# chipshouter-pico-hv.net
KiCad netlist of a schematic drawn in Altium Designer
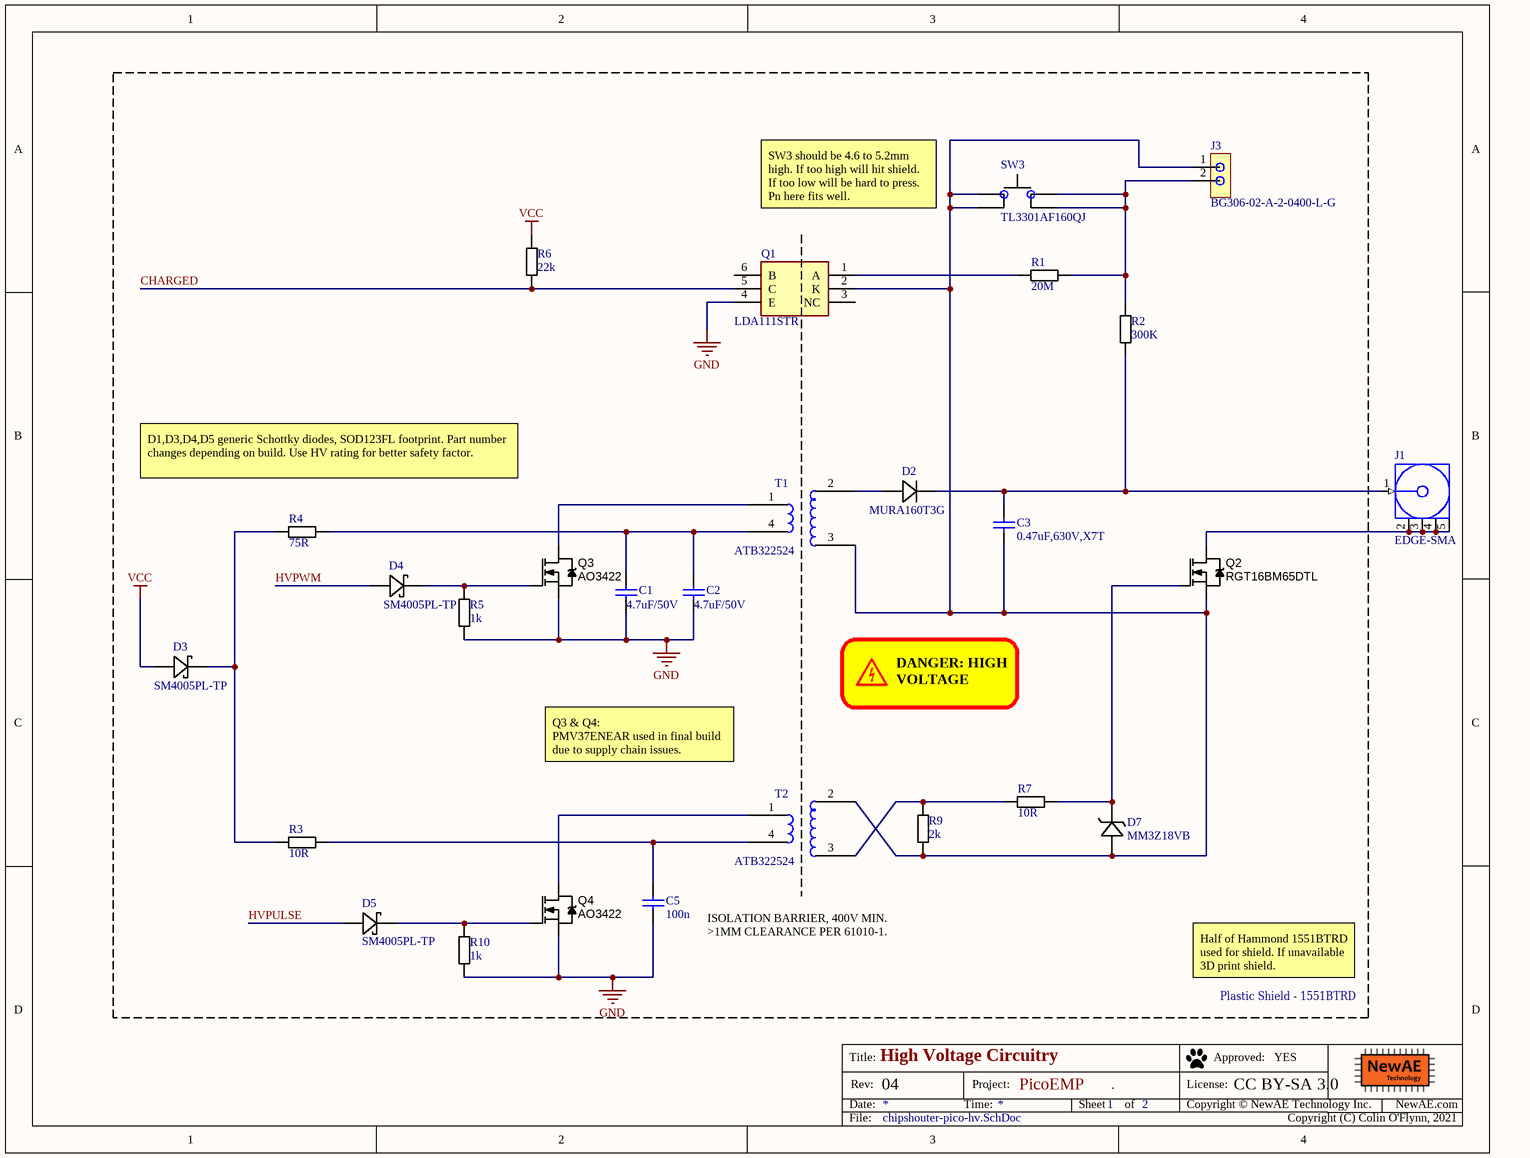
[diagram p0: chipshouter-pico-hv.SchDoc]

(export (version "E")
  (design (tool "Eeschema 10.0.6"))
  (components
    (comp (ref "C1")
      (value "4.7uF/50V")
      (footprint "CAPC0805_M")
      (description "4u7, 50V, 0805, Ceramic")
      (fields (field (name "PART NUMBER") "CCHIP-4u7-0805-50V") (field (name "TOLERANCE") "10%"))
      (libsource (lib "NewAE_AltiumLib") (part "CAP"))
    )
    (comp (ref "C2")
      (value "4.7uF/50V")
      (footprint "CAPC0805_M")
      (description "4u7, 50V, 0805, Ceramic")
      (fields (field (name "PART NUMBER") "CCHIP-4u7-0805-50V") (field (name "TOLERANCE") "10%"))
      (libsource (lib "NewAE_AltiumLib") (part "CAP"))
    )
    (comp (ref "C3")
      (value "0.47uF,630V,X7T")
      (footprint "CKG57N_2220")
      (description "1uF, 630V, X7T, Stacked")
      (fields (field (name "PART NUMBER") "KRM55TR72J474MH01K") (field (name "TOLERANCE") "+22/-30"))
      (libsource (lib "NewAE_AltiumLib") (part "CAP"))
    )
    (comp (ref "C5")
      (value "100n")
      (footprint "CAPC0603_M")
      (description "100n, 0603")
      (fields (field (name "PART NUMBER") "CCHIP-100n-0603"))
      (libsource (lib "NewAE_AltiumLib") (part "CAP"))
    )
    (comp (ref "D2")
      (value "MURA160T3G")
      (footprint "DO-214AC")
      (description "600V, 2A, Fast Recovery Diode")
      (libsource (lib "NewAE_AltiumLib") (part "DIODE"))
    )
    (comp (ref "D3")
      (value "SM4005PL-TP")
      (footprint "DSS13UTR")
      (description "SCHOTTKY 30V SOD-123FL")
      (fields (field (name "PART NUMBER") "DSS13UTR"))
      (libsource (lib "NewAE_AltiumLib") (part "DIODE_SCHOTTKY"))
    )
    (comp (ref "D4")
      (value "SM4005PL-TP")
      (footprint "DSS13UTR")
      (description "SCHOTTKY 30V SOD-123FL")
      (fields (field (name "PART NUMBER") "DSS13UTR"))
      (libsource (lib "NewAE_AltiumLib") (part "DIODE_SCHOTTKY"))
    )
    (comp (ref "D5")
      (value "SM4005PL-TP")
      (footprint "DSS13UTR")
      (description "SCHOTTKY 30V SOD-123FL")
      (fields (field (name "PART NUMBER") "DSS13UTR"))
      (libsource (lib "NewAE_AltiumLib") (part "DIODE_SCHOTTKY"))
    )
    (comp (ref "D7")
      (value "MM3Z18VB")
      (footprint "SOD323")
      (description "DIODE ZENER 10V 400MW SOD323")
      (fields (field (name "TOLERANCE") "2%"))
      (libsource (lib "NewAE_AltiumLib") (part "DIODE_ZENER"))
    )
    (comp (ref "J1")
      (value "EDGE-SMA")
      (footprint "CON-SMA-MALE-PCB-EDGE062")
      (description "SMA MaleEdge Mount Connector for 0.062\" Thick Board")
      (fields (field (name "PART NUMBER") "CON-F-SMA-PCBEDGE-003.062"))
      (libsource (lib "NewAE_AltiumLib") (part "CON-SMA-PCBEDGE-003.062"))
    )
    (comp (ref "J3")
      (value "BG306-02-A-2-0400-L-G")
      (footprint "BG306-R2-2PIN")
      (description "2-Pin SMD, Female Header, 0.1\" spacing")
      (libsource (lib "NewAE_AltiumLib") (part "CON2"))
    )
    (comp (ref "Q1")
      (value "LDA111STR")
      (footprint "SamacSys:SOP254P952X470-6N")
      (description "Phototransistor")
      (fields (field (name "MOUSER PART NUMBER") "849-LDA111STR"))
      (libsource (lib "*") (part "LDA111STR"))
    )
    (comp (ref "Q2")
      (value "RGT16BM65DTL")
      (footprint "DPAK_TO-252AA_M")
      (description "MOSFET N-CH 100V 7.7A DPAK")
      (fields (field (name "PART NUMBER") "IRLR120TRPBF"))
      (libsource (lib "NewAE_AltiumLib") (part "MOSFET_N_GSD"))
    )
    (comp (ref "Q3")
      (value "AO3422")
      (footprint "SOT95P245X110-3M")
      (description "MOSFET N-CH 30V 2.2A SOT23-3")
      (fields (field (name "PART NUMBER") "DMN3200U-7"))
      (libsource (lib "NewAE_AltiumLib") (part "MOSFET_N_GSD"))
    )
    (comp (ref "Q4")
      (value "AO3422")
      (footprint "SOT95P245X110-3M")
      (description "MOSFET N-CH 30V 2.2A SOT23-3")
      (fields (field (name "PART NUMBER") "DMN3200U-7"))
      (libsource (lib "NewAE_AltiumLib") (part "MOSFET_N_GSD"))
    )
    (comp (ref "R1")
      (value "20M")
      (footprint "RESC5025X06N")
      (description "20M, 2010, 1%")
      (fields (field (name "PART NUMBER") "RCHIP-20M-2010") (field (name "TOLERANCE") "1%"))
      (libsource (lib "") (part "RES-EU_1"))
    )
    (comp (ref "R2")
      (value "300K")
      (footprint "RESC6432X06N")
      (description "300K res, 2512, 1%, 3W")
      (fields (field (name "PART NUMBER") "RCHIP-300K-2512") (field (name "TOLERANCE") "1%"))
      (libsource (lib "NewAE_AltiumLib") (part "RES-EU"))
    )
    (comp (ref "R3")
      (value "10R")
      (footprint "RESC1608X55N")
      (description "10R res, 0603, 1%, 1/10W")
      (fields (field (name "PART NUMBER") "RCHIP-10R-0603") (field (name "TOLERANCE") "1%"))
      (libsource (lib "") (part "RES-EU_1"))
    )
    (comp (ref "R4")
      (value "75R")
      (footprint "RESC2012X70N")
      (description "75R res, 0805, 1%, 1/8W")
      (fields (field (name "PART NUMBER") "RCHIP-75R-0805") (field (name "TOLERANCE") "1%"))
      (libsource (lib "") (part "RES-EU_1"))
    )
    (comp (ref "R5")
      (value "1k")
      (footprint "RESC1608X55N")
      (description "1k res, 0603, 1%, 1/10W")
      (fields (field (name "PART NUMBER") "RCHIP-1K-0603") (field (name "TOLERANCE") "1%"))
      (libsource (lib "NewAE_AltiumLib") (part "RES-EU"))
    )
    (comp (ref "R6")
      (value "22k")
      (footprint "RESC1608X55N")
      (description "22k res, 0603, 1%, 1/10W")
      (fields (field (name "PART NUMBER") "RCHIP-22K-0603") (field (name "TOLERANCE") "1%"))
      (libsource (lib "NewAE_AltiumLib") (part "RES-EU"))
    )
    (comp (ref "R7")
      (value "10R")
      (footprint "RESC1608X55N")
      (description "10R res, 0603, 1%, 1/10W")
      (fields (field (name "PART NUMBER") "RCHIP-10R-0603") (field (name "TOLERANCE") "1%"))
      (libsource (lib "") (part "RES-EU_1"))
    )
    (comp (ref "R9")
      (value "2k")
      (footprint "RESC2012X70N")
      (fields (field (name "PART NUMBER") "RCHIP-75R-0805") (field (name "TOLERANCE") "1%"))
      (libsource (lib "NewAE_AltiumLib") (part "RES-EU"))
    )
    (comp (ref "R10")
      (value "1k")
      (footprint "RESC1608X55N")
      (description "1k res, 0603, 1%, 1/10W")
      (fields (field (name "PART NUMBER") "RCHIP-1K-0603") (field (name "TOLERANCE") "1%"))
      (libsource (lib "NewAE_AltiumLib") (part "RES-EU"))
    )
    (comp (ref "SW3")
      (value "TL3301AF160QJ")
      (footprint "CK_KSC7J")
      (description "SWITCH TACTILE SPST-NO 0.01A 32V")
      (fields (field (name "PART NUMBER") "TACTSW-KSC741J"))
      (libsource (lib "NewAE_AltiumLib") (part "SW_PB_NO_4PIN_TACT"))
    )
    (comp (ref "T1")
      (value "ATB322524")
      (footprint "ATB322524_CHUNKY")
      (description "HV Transformer 1:10, Small")
      (fields (field (name "PART NUMBER") "ATB322524_PROTO"))
      (libsource (lib "NewAE_AltiumLib") (part "xformer_2_2_hv"))
    )
    (comp (ref "T2")
      (value "ATB322524")
      (footprint "ATB322524_CHUNKY")
      (description "HV Transformer 1:10, Small")
      (fields (field (name "PART NUMBER") "ATB322524_PROTO"))
      (libsource (lib "NewAE_AltiumLib") (part "xformer_2_2_hv"))
    )
  )
  (nets
    (net (code "1") (name "/CHARGED") (class "Default")
      (node (ref "Q1") (pin "5") (pinfunction "C_5") (pintype "passive"))
      (node (ref "R6") (pin "2") (pinfunction "2_2") (pintype "passive"))
    )
    (net (code "2") (name "/HVPULSE") (class "Default")
      (node (ref "D5") (pin "A") (pinfunction "A_A") (pintype "passive"))
    )
    (net (code "3") (name "/HVPWM") (class "Default")
      (node (ref "D4") (pin "A") (pinfunction "A_A") (pintype "passive"))
    )
    (net (code "4") (name "GND") (class "Default")
      (node (ref "C1") (pin "2") (pinfunction "2_2") (pintype "passive"))
      (node (ref "C2") (pin "2") (pinfunction "2_2") (pintype "passive"))
      (node (ref "C5") (pin "2") (pinfunction "2_2") (pintype "passive"))
      (node (ref "Q1") (pin "4") (pinfunction "E_4") (pintype "passive"))
      (node (ref "Q3") (pin "2") (pinfunction "S_2") (pintype "passive"))
      (node (ref "Q4") (pin "2") (pinfunction "S_2") (pintype "passive"))
      (node (ref "R10") (pin "2") (pinfunction "2_2") (pintype "passive"))
      (node (ref "R5") (pin "2") (pinfunction "2_2") (pintype "passive"))
    )
    (net (code "5") (name "Net-(C1-Pad1)") (class "Default")
      (node (ref "C1") (pin "1") (pinfunction "1_1") (pintype "passive"))
      (node (ref "C2") (pin "1") (pinfunction "1_1") (pintype "passive"))
      (node (ref "R4") (pin "2") (pinfunction "2_2") (pintype "passive"))
      (node (ref "T1") (pin "4") (pinfunction "4_4") (pintype "passive"))
    )
    (net (code "6") (name "Net-(C5-Pad1)") (class "Default")
      (node (ref "C5") (pin "1") (pinfunction "1_1") (pintype "passive"))
      (node (ref "R3") (pin "2") (pinfunction "2_2") (pintype "passive"))
      (node (ref "T2") (pin "4") (pinfunction "4_4") (pintype "passive"))
    )
    (net (code "7") (name "Net-(D2-PadA)") (class "Default")
      (node (ref "D2") (pin "A") (pinfunction "A_A") (pintype "passive"))
      (node (ref "T1") (pin "2") (pinfunction "2_2") (pintype "passive"))
    )
    (net (code "8") (name "Net-(D3-PadK)") (class "Default")
      (node (ref "D3") (pin "K") (pinfunction "K_K") (pintype "passive"))
      (node (ref "R3") (pin "1") (pinfunction "1_1") (pintype "passive"))
      (node (ref "R4") (pin "1") (pinfunction "1_1") (pintype "passive"))
    )
    (net (code "9") (name "Net-(J1-Signal)") (class "Default")
      (node (ref "C3") (pin "1") (pinfunction "1_1") (pintype "passive"))
      (node (ref "D2") (pin "K") (pinfunction "K_K") (pintype "passive"))
      (node (ref "J1") (pin "1") (pinfunction "Signal_1") (pintype "input"))
      (node (ref "R2") (pin "2") (pinfunction "2_2") (pintype "passive"))
    )
    (net (code "10") (name "Net-(J3-Pad2)") (class "Default")
      (node (ref "J3") (pin "2") (pinfunction "2_2") (pintype "passive"))
      (node (ref "R1") (pin "2") (pinfunction "2_2") (pintype "passive"))
      (node (ref "R2") (pin "1") (pinfunction "1_1") (pintype "passive"))
      (node (ref "SW3") (pin "2") (pinfunction "IN_2") (pintype "passive"))
      (node (ref "SW3") (pin "3") (pinfunction "IN_3") (pintype "passive"))
    )
    (net (code "11") (name "Net-(Q1-A)") (class "Default")
      (node (ref "Q1") (pin "1") (pinfunction "A_1") (pintype "passive"))
      (node (ref "R1") (pin "1") (pinfunction "1_1") (pintype "passive"))
    )
    (net (code "12") (name "Net-(Q1-K)") (class "Default")
      (node (ref "C3") (pin "2") (pinfunction "2_2") (pintype "passive"))
      (node (ref "D7") (pin "A") (pinfunction "A_A") (pintype "passive"))
      (node (ref "J3") (pin "1") (pinfunction "1_1") (pintype "passive"))
      (node (ref "Q1") (pin "2") (pinfunction "K_2") (pintype "passive"))
      (node (ref "Q2") (pin "2") (pinfunction "S_2") (pintype "passive"))
      (node (ref "R9") (pin "2") (pinfunction "2_2") (pintype "passive"))
      (node (ref "SW3") (pin "1") (pinfunction "IN_1") (pintype "passive"))
      (node (ref "SW3") (pin "4") (pinfunction "IN_4") (pintype "passive"))
      (node (ref "T1") (pin "3") (pinfunction "3_3") (pintype "passive"))
      (node (ref "T2") (pin "2") (pinfunction "2_2") (pintype "passive"))
    )
    (net (code "13") (name "Net-(Q2-D)") (class "Default")
      (node (ref "J1") (pin "2") (pinfunction "GND_2") (pintype "power_in"))
      (node (ref "J1") (pin "3") (pinfunction "GND_3") (pintype "power_in"))
      (node (ref "J1") (pin "4") (pinfunction "GND_4") (pintype "power_in"))
      (node (ref "J1") (pin "5") (pinfunction "GND_5") (pintype "power_in"))
      (node (ref "Q2") (pin "3") (pinfunction "D_3") (pintype "passive"))
    )
    (net (code "14") (name "Net-(Q2-G)") (class "Default")
      (node (ref "D7") (pin "K") (pinfunction "K_K") (pintype "passive"))
      (node (ref "Q2") (pin "1") (pinfunction "G_1") (pintype "passive"))
      (node (ref "R7") (pin "2") (pinfunction "2_2") (pintype "passive"))
    )
    (net (code "15") (name "Net-(Q3-D)") (class "Default")
      (node (ref "Q3") (pin "3") (pinfunction "D_3") (pintype "passive"))
      (node (ref "T1") (pin "1") (pinfunction "1_1") (pintype "passive"))
    )
    (net (code "16") (name "Net-(Q3-G)") (class "Default")
      (node (ref "D4") (pin "K") (pinfunction "K_K") (pintype "passive"))
      (node (ref "Q3") (pin "1") (pinfunction "G_1") (pintype "passive"))
      (node (ref "R5") (pin "1") (pinfunction "1_1") (pintype "passive"))
    )
    (net (code "17") (name "Net-(Q4-D)") (class "Default")
      (node (ref "Q4") (pin "3") (pinfunction "D_3") (pintype "passive"))
      (node (ref "T2") (pin "1") (pinfunction "1_1") (pintype "passive"))
    )
    (net (code "18") (name "Net-(Q4-G)") (class "Default")
      (node (ref "D5") (pin "K") (pinfunction "K_K") (pintype "passive"))
      (node (ref "Q4") (pin "1") (pinfunction "G_1") (pintype "passive"))
      (node (ref "R10") (pin "1") (pinfunction "1_1") (pintype "passive"))
    )
    (net (code "19") (name "Net-(R7-Pad1)") (class "Default")
      (node (ref "R7") (pin "1") (pinfunction "1_1") (pintype "passive"))
      (node (ref "R9") (pin "1") (pinfunction "1_1") (pintype "passive"))
      (node (ref "T2") (pin "3") (pinfunction "3_3") (pintype "passive"))
    )
    (net (code "20") (name "VCC") (class "Default")
      (node (ref "D3") (pin "A") (pinfunction "A_A") (pintype "passive"))
      (node (ref "R6") (pin "1") (pinfunction "1_1") (pintype "passive"))
    )
    (net (code "21") (name "unconnected-(Q1-B-Pad6)") (class "Default")
      (node (ref "Q1") (pin "6") (pinfunction "B_6") (pintype "passive"))
    )
    (net (code "22") (name "unconnected-(Q1-NC-Pad3)") (class "Default")
      (node (ref "Q1") (pin "3") (pinfunction "NC_3") (pintype "passive"))
    )
  )
)
